# Tracksoar_v2_flash_shield_test.net
KiCad netlist of a schematic drawn in EAGLE
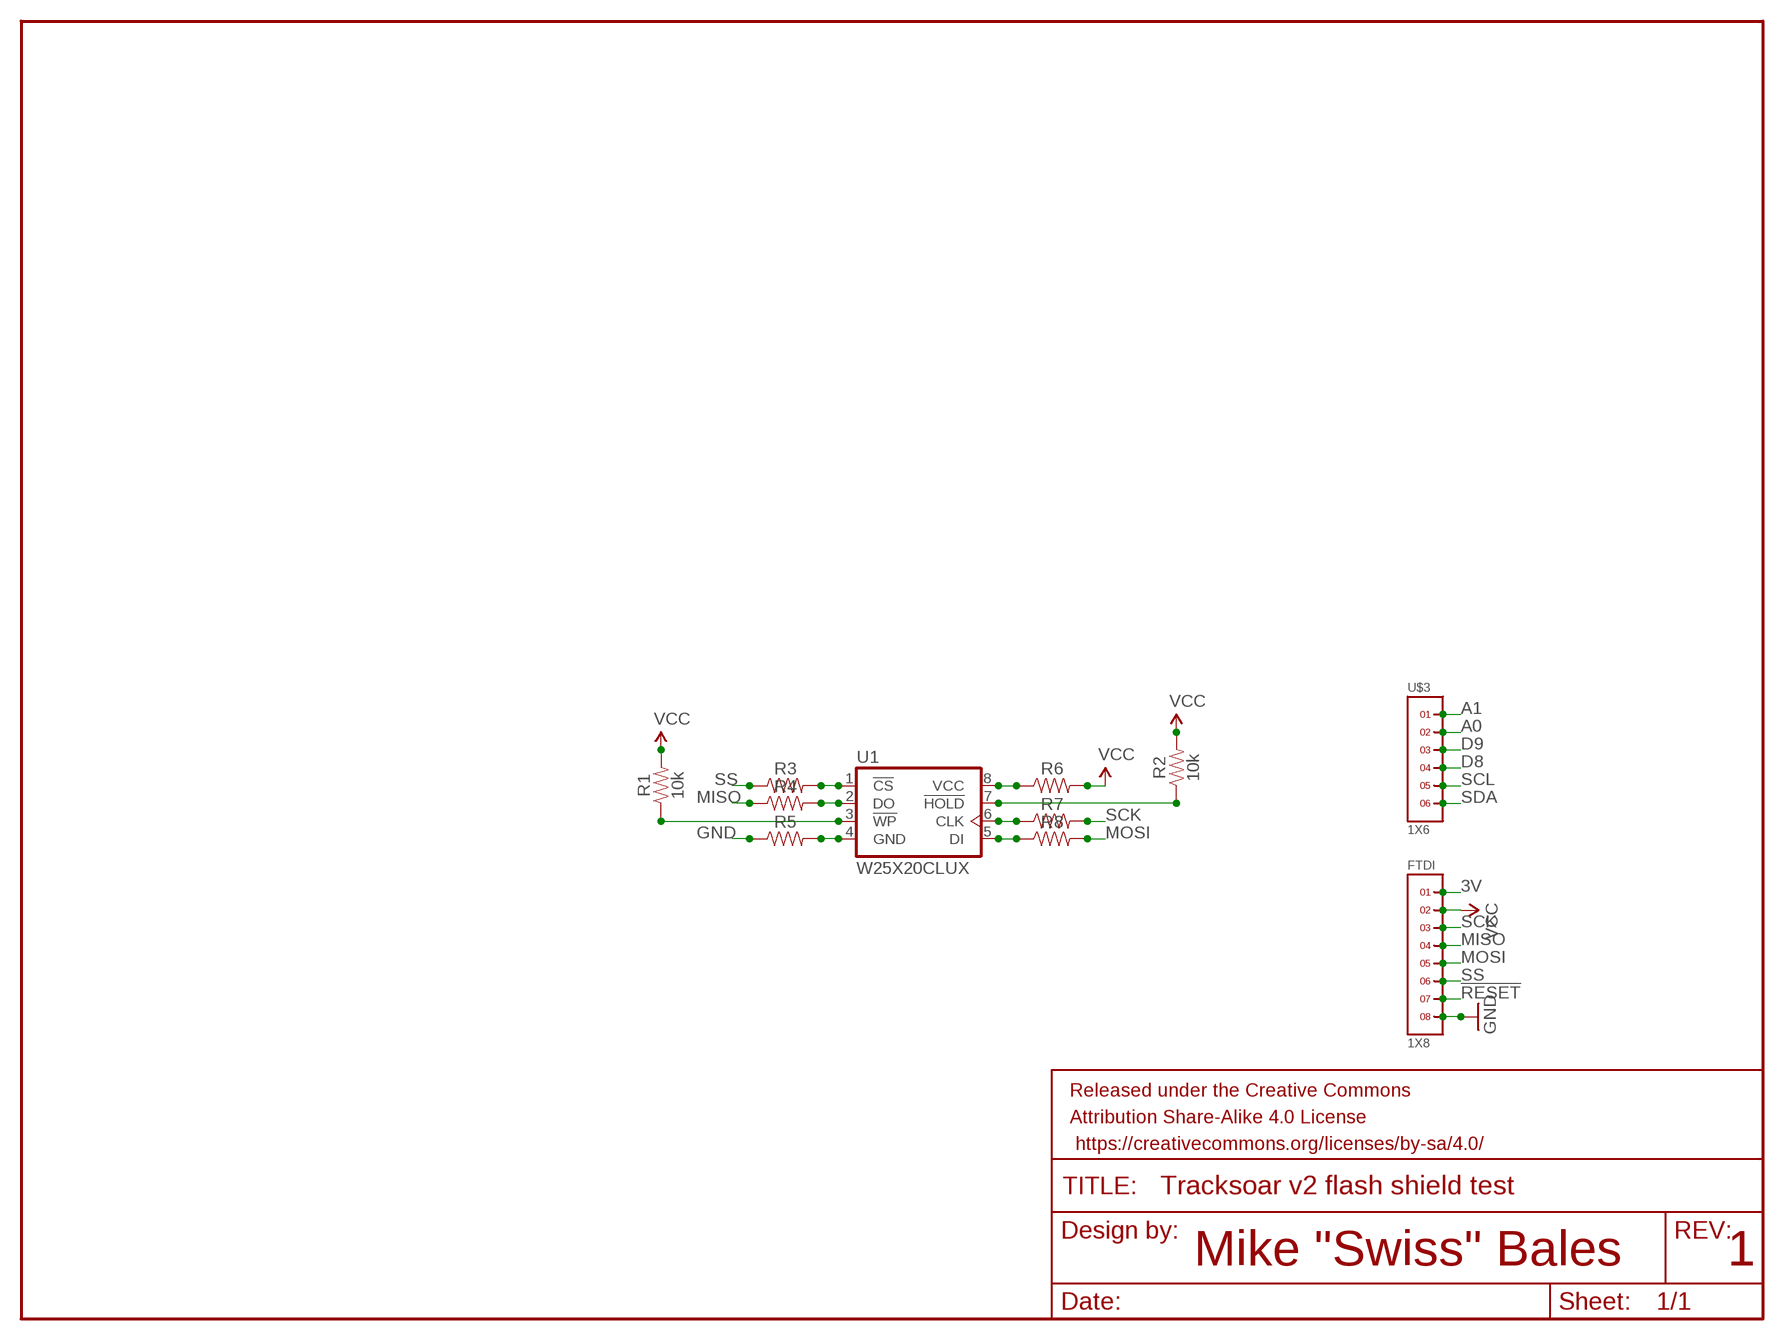
[diagram p0: schematic, sheet 1]

(export (version "E")
  (design (tool "Eeschema 10.0.6"))
  (components
    (comp (ref "FRAME1")
      (value "FRAME-LETTER")
      (footprint "eagle-import:CREATIVE_COMMONS")
      (libsource (lib "eagle-import") (part "FRAME-LETTER"))
    )
    (comp (ref "FTDI")
      (value "1X8")
      (footprint "eagle-import:1X8")
      (libsource (lib "eagle-import") (part "1X8"))
    )
    (comp (ref "R1")
      (value "10k")
      (footprint "eagle-import:0603")
      (libsource (lib "eagle-import") (part "10KOHM-0603-1/10W-1%"))
    )
    (comp (ref "R2")
      (value "10k")
      (footprint "eagle-import:0603")
      (libsource (lib "eagle-import") (part "10KOHM-0603-1/10W-1%"))
    )
    (comp (ref "R3")
      (value "RESISTOR0603")
      (footprint "eagle-import:0603")
      (libsource (lib "eagle-import") (part "RESISTOR0603"))
    )
    (comp (ref "R4")
      (value "RESISTOR0603")
      (footprint "eagle-import:0603")
      (libsource (lib "eagle-import") (part "RESISTOR0603"))
    )
    (comp (ref "R5")
      (value "RESISTOR0603")
      (footprint "eagle-import:0603")
      (libsource (lib "eagle-import") (part "RESISTOR0603"))
    )
    (comp (ref "R6")
      (value "RESISTOR0603")
      (footprint "eagle-import:0603")
      (libsource (lib "eagle-import") (part "RESISTOR0603"))
    )
    (comp (ref "R7")
      (value "RESISTOR0603")
      (footprint "eagle-import:0603")
      (libsource (lib "eagle-import") (part "RESISTOR0603"))
    )
    (comp (ref "R8")
      (value "RESISTOR0603")
      (footprint "eagle-import:0603")
      (libsource (lib "eagle-import") (part "RESISTOR0603"))
    )
    (comp (ref "U$3")
      (value "1X6")
      (footprint "eagle-import:1X6")
      (libsource (lib "eagle-import") (part "1X6"))
    )
    (comp (ref "U1")
      (value "W25X20CLUX")
      (footprint "eagle-import:SON-8-50P-300W-200L-100H-40F-20EW-165EL")
      (libsource (lib "eagle-import") (part "W25X20CLUX"))
    )
  )
  (nets
    (net (code "1") (name "/3V") (class "Default")
      (node (ref "FTDI") (pin "1") (pinfunction "1_1") (pintype "bidirectional"))
    )
    (net (code "2") (name "/A0") (class "Default")
      (node (ref "U$3") (pin "2") (pinfunction "2_2") (pintype "bidirectional"))
    )
    (net (code "3") (name "/A1") (class "Default")
      (node (ref "U$3") (pin "1") (pinfunction "1_1") (pintype "bidirectional"))
    )
    (net (code "4") (name "/D8") (class "Default")
      (node (ref "U$3") (pin "4") (pinfunction "4_4") (pintype "bidirectional"))
    )
    (net (code "5") (name "/D9") (class "Default")
      (node (ref "U$3") (pin "3") (pinfunction "3_3") (pintype "bidirectional"))
    )
    (net (code "6") (name "/MISO") (class "Default")
      (node (ref "FTDI") (pin "4") (pinfunction "4_4") (pintype "bidirectional"))
      (node (ref "R4") (pin "1") (pinfunction "1_1") (pintype "passive"))
    )
    (net (code "7") (name "/MOSI") (class "Default")
      (node (ref "FTDI") (pin "5") (pinfunction "5_5") (pintype "bidirectional"))
      (node (ref "R8") (pin "2") (pinfunction "2_2") (pintype "passive"))
    )
    (net (code "8") (name "/SCK") (class "Default")
      (node (ref "FTDI") (pin "3") (pinfunction "3_3") (pintype "bidirectional"))
      (node (ref "R7") (pin "2") (pinfunction "2_2") (pintype "passive"))
    )
    (net (code "9") (name "/SCL") (class "Default")
      (node (ref "U$3") (pin "5") (pinfunction "5_5") (pintype "bidirectional"))
    )
    (net (code "10") (name "/SDA") (class "Default")
      (node (ref "U$3") (pin "6") (pinfunction "6_6") (pintype "bidirectional"))
    )
    (net (code "11") (name "/SS") (class "Default")
      (node (ref "FTDI") (pin "6") (pinfunction "6_6") (pintype "bidirectional"))
      (node (ref "R3") (pin "1") (pinfunction "1_1") (pintype "passive"))
    )
    (net (code "12") (name "/~{RESET}") (class "Default")
      (node (ref "FTDI") (pin "7") (pinfunction "7_7") (pintype "bidirectional"))
    )
    (net (code "13") (name "GND") (class "Default")
      (node (ref "FTDI") (pin "8") (pinfunction "8_8") (pintype "bidirectional"))
      (node (ref "R5") (pin "1") (pinfunction "1_1") (pintype "passive"))
    )
    (net (code "14") (name "Net-(U1-CLK)") (class "Default")
      (node (ref "R7") (pin "1") (pinfunction "1_1") (pintype "passive"))
      (node (ref "U1") (pin "6") (pinfunction "CLK_6") (pintype "input"))
    )
    (net (code "15") (name "Net-(U1-DI)") (class "Default")
      (node (ref "R8") (pin "1") (pinfunction "1_1") (pintype "passive"))
      (node (ref "U1") (pin "5") (pinfunction "DI_5") (pintype "input"))
    )
    (net (code "16") (name "Net-(U1-DO)") (class "Default")
      (node (ref "R4") (pin "2") (pinfunction "2_2") (pintype "passive"))
      (node (ref "U1") (pin "2") (pinfunction "DO_2") (pintype "output"))
    )
    (net (code "17") (name "Net-(U1-GND)") (class "Default")
      (node (ref "R5") (pin "2") (pinfunction "2_2") (pintype "passive"))
      (node (ref "U1") (pin "4") (pinfunction "GND_4") (pintype "power_in"))
    )
    (net (code "18") (name "Net-(U1-VCC)") (class "Default")
      (node (ref "R6") (pin "1") (pinfunction "1_1") (pintype "passive"))
      (node (ref "U1") (pin "8") (pinfunction "VCC_8") (pintype "power_in"))
    )
    (net (code "19") (name "Net-(U1-~{CS})") (class "Default")
      (node (ref "R3") (pin "2") (pinfunction "2_2") (pintype "passive"))
      (node (ref "U1") (pin "1") (pinfunction "~{CS}_1") (pintype "input"))
    )
    (net (code "20") (name "Net-(U1-~{HOLD})") (class "Default")
      (node (ref "R2") (pin "1") (pinfunction "1_1") (pintype "passive"))
      (node (ref "U1") (pin "7") (pinfunction "~{HOLD}_7") (pintype "input"))
    )
    (net (code "21") (name "Net-(U1-~{WP})") (class "Default")
      (node (ref "R1") (pin "1") (pinfunction "1_1") (pintype "passive"))
      (node (ref "U1") (pin "3") (pinfunction "~{WP}_3") (pintype "input"))
    )
    (net (code "22") (name "VCC") (class "Default")
      (node (ref "FTDI") (pin "2") (pinfunction "2_2") (pintype "bidirectional"))
      (node (ref "R1") (pin "2") (pinfunction "2_2") (pintype "passive"))
      (node (ref "R2") (pin "2") (pinfunction "2_2") (pintype "passive"))
      (node (ref "R6") (pin "2") (pinfunction "2_2") (pintype "passive"))
    )
  )
)
